# Distro_schematic.net
KiCad netlist of a schematic drawn in Altium Designer
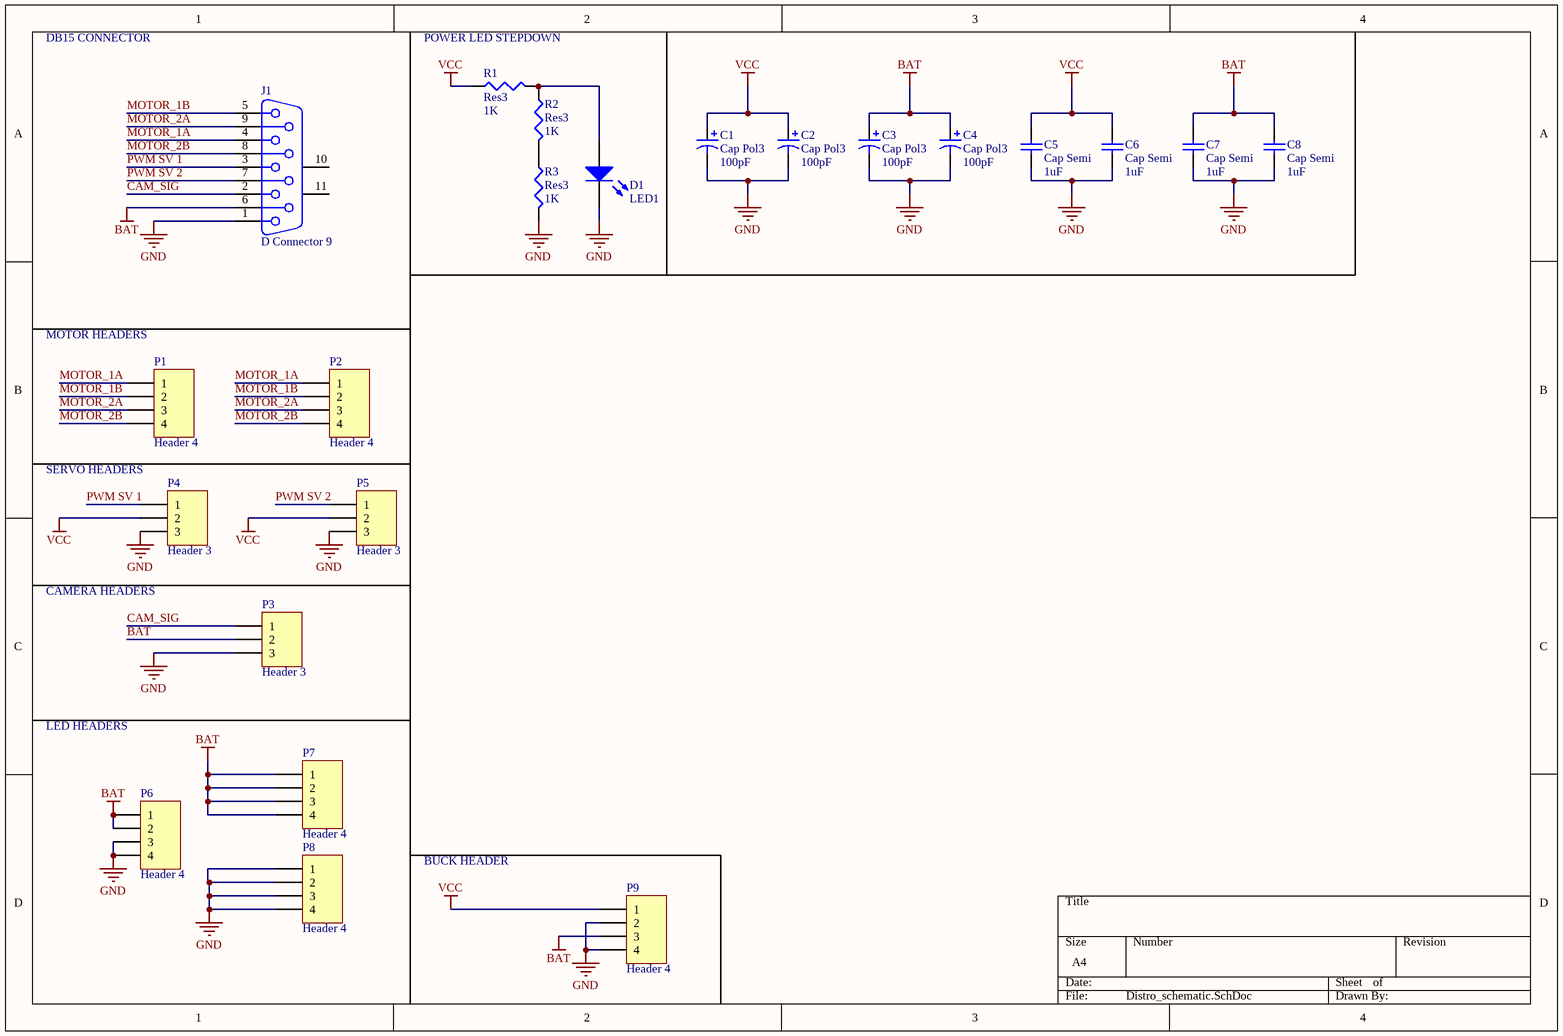
[diagram p0: Distro_schematic.SchDoc]

(export (version "E")
  (design (tool "Eeschema 10.0.6"))
  (components
    (comp (ref "C1")
      (value "Cap Pol3")
      (footprint "C0805")
      (description "Polarized Capacitor (Surface Mount)")
      (fields (field (name "ALTIUM_VALUE") "100pF") (field (name "PUBLISHER") "Altium Limited"))
      (libsource (lib "Miscellaneous Devices") (part "Cap Pol3"))
    )
    (comp (ref "C2")
      (value "Cap Pol3")
      (footprint "C0805")
      (description "Polarized Capacitor (Surface Mount)")
      (fields (field (name "ALTIUM_VALUE") "100pF") (field (name "PUBLISHER") "Altium Limited"))
      (libsource (lib "Miscellaneous Devices") (part "Cap Pol3"))
    )
    (comp (ref "C3")
      (value "Cap Pol3")
      (footprint "C0805")
      (description "Polarized Capacitor (Surface Mount)")
      (fields (field (name "ALTIUM_VALUE") "100pF") (field (name "PUBLISHER") "Altium Limited"))
      (libsource (lib "Miscellaneous Devices") (part "Cap Pol3"))
    )
    (comp (ref "C4")
      (value "Cap Pol3")
      (footprint "C0805")
      (description "Polarized Capacitor (Surface Mount)")
      (fields (field (name "ALTIUM_VALUE") "100pF") (field (name "PUBLISHER") "Altium Limited"))
      (libsource (lib "Miscellaneous Devices") (part "Cap Pol3"))
    )
    (comp (ref "C5")
      (value "Cap Semi")
      (footprint "C1206")
      (description "Capacitor (Semiconductor SIM Model)")
      (fields (field (name "ALTIUM_VALUE") "1uF") (field (name "PUBLISHER") "Altium Limited"))
      (libsource (lib "Miscellaneous Devices") (part "Cap Semi"))
    )
    (comp (ref "C6")
      (value "Cap Semi")
      (footprint "C1206")
      (description "Capacitor (Semiconductor SIM Model)")
      (fields (field (name "ALTIUM_VALUE") "1uF") (field (name "PUBLISHER") "Altium Limited"))
      (libsource (lib "Miscellaneous Devices") (part "Cap Semi"))
    )
    (comp (ref "C7")
      (value "Cap Semi")
      (footprint "C1206")
      (description "Capacitor (Semiconductor SIM Model)")
      (fields (field (name "ALTIUM_VALUE") "1uF") (field (name "PUBLISHER") "Altium Limited"))
      (libsource (lib "Miscellaneous Devices") (part "Cap Semi"))
    )
    (comp (ref "C8")
      (value "Cap Semi")
      (footprint "C1206")
      (description "Capacitor (Semiconductor SIM Model)")
      (fields (field (name "ALTIUM_VALUE") "1uF") (field (name "PUBLISHER") "Altium Limited"))
      (libsource (lib "Miscellaneous Devices") (part "Cap Semi"))
    )
    (comp (ref "D1")
      (value "LED1")
      (footprint "L0603")
      (description "Typical RED GaAs LED")
      (fields (field (name "PUBLISHER") "Altium Limited"))
      (libsource (lib "Miscellaneous Devices") (part "LED1"))
    )
    (comp (ref "J1")
      (value "D Connector 9")
      (footprint "DSUB1.385-2H9")
      (description "Receptacle Assembly, 9 Position, Right Angle")
      (fields (field (name "PUBLISHER") "Altium Limited"))
      (libsource (lib "Miscellaneous Connectors") (part "D Connector 9"))
    )
    (comp (ref "P1")
      (value "Header 4")
      (footprint "HDR1X4")
      (description "Header, 4-Pin")
      (fields (field (name "PUBLISHER") "Altium Limited"))
      (libsource (lib "Miscellaneous Connectors") (part "Header 4"))
    )
    (comp (ref "P2")
      (value "Header 4")
      (footprint "HDR1X4")
      (description "Header, 4-Pin")
      (fields (field (name "PUBLISHER") "Altium Limited"))
      (libsource (lib "Miscellaneous Connectors") (part "Header 4"))
    )
    (comp (ref "P3")
      (value "Header 3")
      (footprint "HDR1X3")
      (description "Header, 3-Pin")
      (fields (field (name "PUBLISHER") "Altium Limited"))
      (libsource (lib "Miscellaneous Connectors") (part "Header 3"))
    )
    (comp (ref "P4")
      (value "Header 3")
      (footprint "HDR1X3")
      (description "Header, 3-Pin")
      (fields (field (name "PUBLISHER") "Altium Limited"))
      (libsource (lib "Miscellaneous Connectors") (part "Header 3"))
    )
    (comp (ref "P5")
      (value "Header 3")
      (footprint "HDR1X3")
      (description "Header, 3-Pin")
      (fields (field (name "PUBLISHER") "Altium Limited"))
      (libsource (lib "Miscellaneous Connectors") (part "Header 3"))
    )
    (comp (ref "P6")
      (value "Header 4")
      (footprint "HDR1X4")
      (description "Header, 4-Pin")
      (fields (field (name "PUBLISHER") "Altium Limited"))
      (libsource (lib "Miscellaneous Connectors") (part "Header 4"))
    )
    (comp (ref "P7")
      (value "Header 4")
      (footprint "HDR1X4")
      (description "Header, 4-Pin")
      (fields (field (name "PUBLISHER") "Altium Limited"))
      (libsource (lib "Miscellaneous Connectors") (part "Header 4"))
    )
    (comp (ref "P8")
      (value "Header 4")
      (footprint "HDR1X4")
      (description "Header, 4-Pin")
      (fields (field (name "PUBLISHER") "Altium Limited"))
      (libsource (lib "Miscellaneous Connectors") (part "Header 4"))
    )
    (comp (ref "P9")
      (value "Header 4")
      (footprint "HDR1X4")
      (description "Header, 4-Pin")
      (fields (field (name "PUBLISHER") "Altium Limited"))
      (libsource (lib "Miscellaneous Connectors") (part "Header 4"))
    )
    (comp (ref "R1")
      (value "Res3")
      (footprint "J1-0603")
      (description "Resistor")
      (fields (field (name "ALTIUM_VALUE") "1K") (field (name "PUBLISHER") "Altium Limited"))
      (libsource (lib "Miscellaneous Devices") (part "Res3"))
    )
    (comp (ref "R2")
      (value "Res3")
      (footprint "J1-0603")
      (description "Resistor")
      (fields (field (name "ALTIUM_VALUE") "1K") (field (name "PUBLISHER") "Altium Limited"))
      (libsource (lib "Miscellaneous Devices") (part "Res3"))
    )
    (comp (ref "R3")
      (value "Res3")
      (footprint "J1-0603")
      (description "Resistor")
      (fields (field (name "ALTIUM_VALUE") "1K") (field (name "PUBLISHER") "Altium Limited"))
      (libsource (lib "Miscellaneous Devices") (part "Res3"))
    )
  )
  (nets
    (net (code "1") (name "/CAM_SIG") (class "Default")
      (node (ref "J1") (pin "2") (pinfunction "2_2") (pintype "passive"))
      (node (ref "P3") (pin "1") (pinfunction "1_1") (pintype "passive"))
    )
    (net (code "2") (name "/MOTOR_1A") (class "Default")
      (node (ref "J1") (pin "4") (pinfunction "4_4") (pintype "passive"))
      (node (ref "P1") (pin "1") (pinfunction "1_1") (pintype "passive"))
      (node (ref "P2") (pin "1") (pinfunction "1_1") (pintype "passive"))
    )
    (net (code "3") (name "/MOTOR_1B") (class "Default")
      (node (ref "J1") (pin "5") (pinfunction "5_5") (pintype "passive"))
      (node (ref "P1") (pin "2") (pinfunction "2_2") (pintype "passive"))
      (node (ref "P2") (pin "2") (pinfunction "2_2") (pintype "passive"))
    )
    (net (code "4") (name "/MOTOR_2A") (class "Default")
      (node (ref "J1") (pin "9") (pinfunction "9_9") (pintype "passive"))
      (node (ref "P1") (pin "3") (pinfunction "3_3") (pintype "passive"))
      (node (ref "P2") (pin "3") (pinfunction "3_3") (pintype "passive"))
    )
    (net (code "5") (name "/MOTOR_2B") (class "Default")
      (node (ref "J1") (pin "8") (pinfunction "8_8") (pintype "passive"))
      (node (ref "P1") (pin "4") (pinfunction "4_4") (pintype "passive"))
      (node (ref "P2") (pin "4") (pinfunction "4_4") (pintype "passive"))
    )
    (net (code "6") (name "/PWM SV 1") (class "Default")
      (node (ref "J1") (pin "3") (pinfunction "3_3") (pintype "passive"))
      (node (ref "P4") (pin "1") (pinfunction "1_1") (pintype "passive"))
    )
    (net (code "7") (name "/PWM SV 2") (class "Default")
      (node (ref "J1") (pin "7") (pinfunction "7_7") (pintype "passive"))
      (node (ref "P5") (pin "1") (pinfunction "1_1") (pintype "passive"))
    )
    (net (code "8") (name "BAT") (class "Default")
      (node (ref "C3") (pin "1") (pinfunction "1_1") (pintype "passive"))
      (node (ref "C4") (pin "1") (pinfunction "1_1") (pintype "passive"))
      (node (ref "C7") (pin "2") (pinfunction "2_2") (pintype "passive"))
      (node (ref "C8") (pin "2") (pinfunction "2_2") (pintype "passive"))
      (node (ref "J1") (pin "6") (pinfunction "6_6") (pintype "passive"))
      (node (ref "P3") (pin "2") (pinfunction "2_2") (pintype "passive"))
      (node (ref "P6") (pin "1") (pinfunction "1_1") (pintype "passive"))
      (node (ref "P6") (pin "2") (pinfunction "2_2") (pintype "passive"))
      (node (ref "P7") (pin "1") (pinfunction "1_1") (pintype "passive"))
      (node (ref "P7") (pin "2") (pinfunction "2_2") (pintype "passive"))
      (node (ref "P7") (pin "3") (pinfunction "3_3") (pintype "passive"))
      (node (ref "P7") (pin "4") (pinfunction "4_4") (pintype "passive"))
      (node (ref "P9") (pin "3") (pinfunction "3_3") (pintype "passive"))
    )
    (net (code "9") (name "GND") (class "Default")
      (node (ref "C1") (pin "2") (pinfunction "2_2") (pintype "passive"))
      (node (ref "C2") (pin "2") (pinfunction "2_2") (pintype "passive"))
      (node (ref "C3") (pin "2") (pinfunction "2_2") (pintype "passive"))
      (node (ref "C4") (pin "2") (pinfunction "2_2") (pintype "passive"))
      (node (ref "C5") (pin "1") (pinfunction "1_1") (pintype "passive"))
      (node (ref "C6") (pin "1") (pinfunction "1_1") (pintype "passive"))
      (node (ref "C7") (pin "1") (pinfunction "1_1") (pintype "passive"))
      (node (ref "C8") (pin "1") (pinfunction "1_1") (pintype "passive"))
      (node (ref "D1") (pin "2") (pinfunction "K_2") (pintype "passive"))
      (node (ref "J1") (pin "1") (pinfunction "1_1") (pintype "passive"))
      (node (ref "P3") (pin "3") (pinfunction "3_3") (pintype "passive"))
      (node (ref "P4") (pin "3") (pinfunction "3_3") (pintype "passive"))
      (node (ref "P5") (pin "3") (pinfunction "3_3") (pintype "passive"))
      (node (ref "P6") (pin "3") (pinfunction "3_3") (pintype "passive"))
      (node (ref "P6") (pin "4") (pinfunction "4_4") (pintype "passive"))
      (node (ref "P8") (pin "1") (pinfunction "1_1") (pintype "passive"))
      (node (ref "P8") (pin "2") (pinfunction "2_2") (pintype "passive"))
      (node (ref "P8") (pin "3") (pinfunction "3_3") (pintype "passive"))
      (node (ref "P8") (pin "4") (pinfunction "4_4") (pintype "passive"))
      (node (ref "P9") (pin "2") (pinfunction "2_2") (pintype "passive"))
      (node (ref "P9") (pin "4") (pinfunction "4_4") (pintype "passive"))
      (node (ref "R3") (pin "2") (pinfunction "2_2") (pintype "passive"))
    )
    (net (code "10") (name "Net-(D1-A)") (class "Default")
      (node (ref "D1") (pin "1") (pinfunction "A_1") (pintype "passive"))
      (node (ref "R1") (pin "2") (pinfunction "2_2") (pintype "passive"))
      (node (ref "R2") (pin "1") (pinfunction "1_1") (pintype "passive"))
    )
    (net (code "11") (name "Net-(R2-Pad2)") (class "Default")
      (node (ref "R2") (pin "2") (pinfunction "2_2") (pintype "passive"))
      (node (ref "R3") (pin "1") (pinfunction "1_1") (pintype "passive"))
    )
    (net (code "12") (name "VCC") (class "Default")
      (node (ref "C1") (pin "1") (pinfunction "1_1") (pintype "passive"))
      (node (ref "C2") (pin "1") (pinfunction "1_1") (pintype "passive"))
      (node (ref "C5") (pin "2") (pinfunction "2_2") (pintype "passive"))
      (node (ref "C6") (pin "2") (pinfunction "2_2") (pintype "passive"))
      (node (ref "P4") (pin "2") (pinfunction "2_2") (pintype "passive"))
      (node (ref "P5") (pin "2") (pinfunction "2_2") (pintype "passive"))
      (node (ref "P9") (pin "1") (pinfunction "1_1") (pintype "passive"))
      (node (ref "R1") (pin "1") (pinfunction "1_1") (pintype "passive"))
    )
    (net (code "13") (name "unconnected-(J1-MH1-Pad10)") (class "Default")
      (node (ref "J1") (pin "10") (pinfunction "MH1_10") (pintype "passive"))
    )
    (net (code "14") (name "unconnected-(J1-MH2-Pad11)") (class "Default")
      (node (ref "J1") (pin "11") (pinfunction "MH2_11") (pintype "passive"))
    )
  )
)
